# lat_stm_zybo_rev2.net
KiCad netlist of a schematic drawn in EAGLE
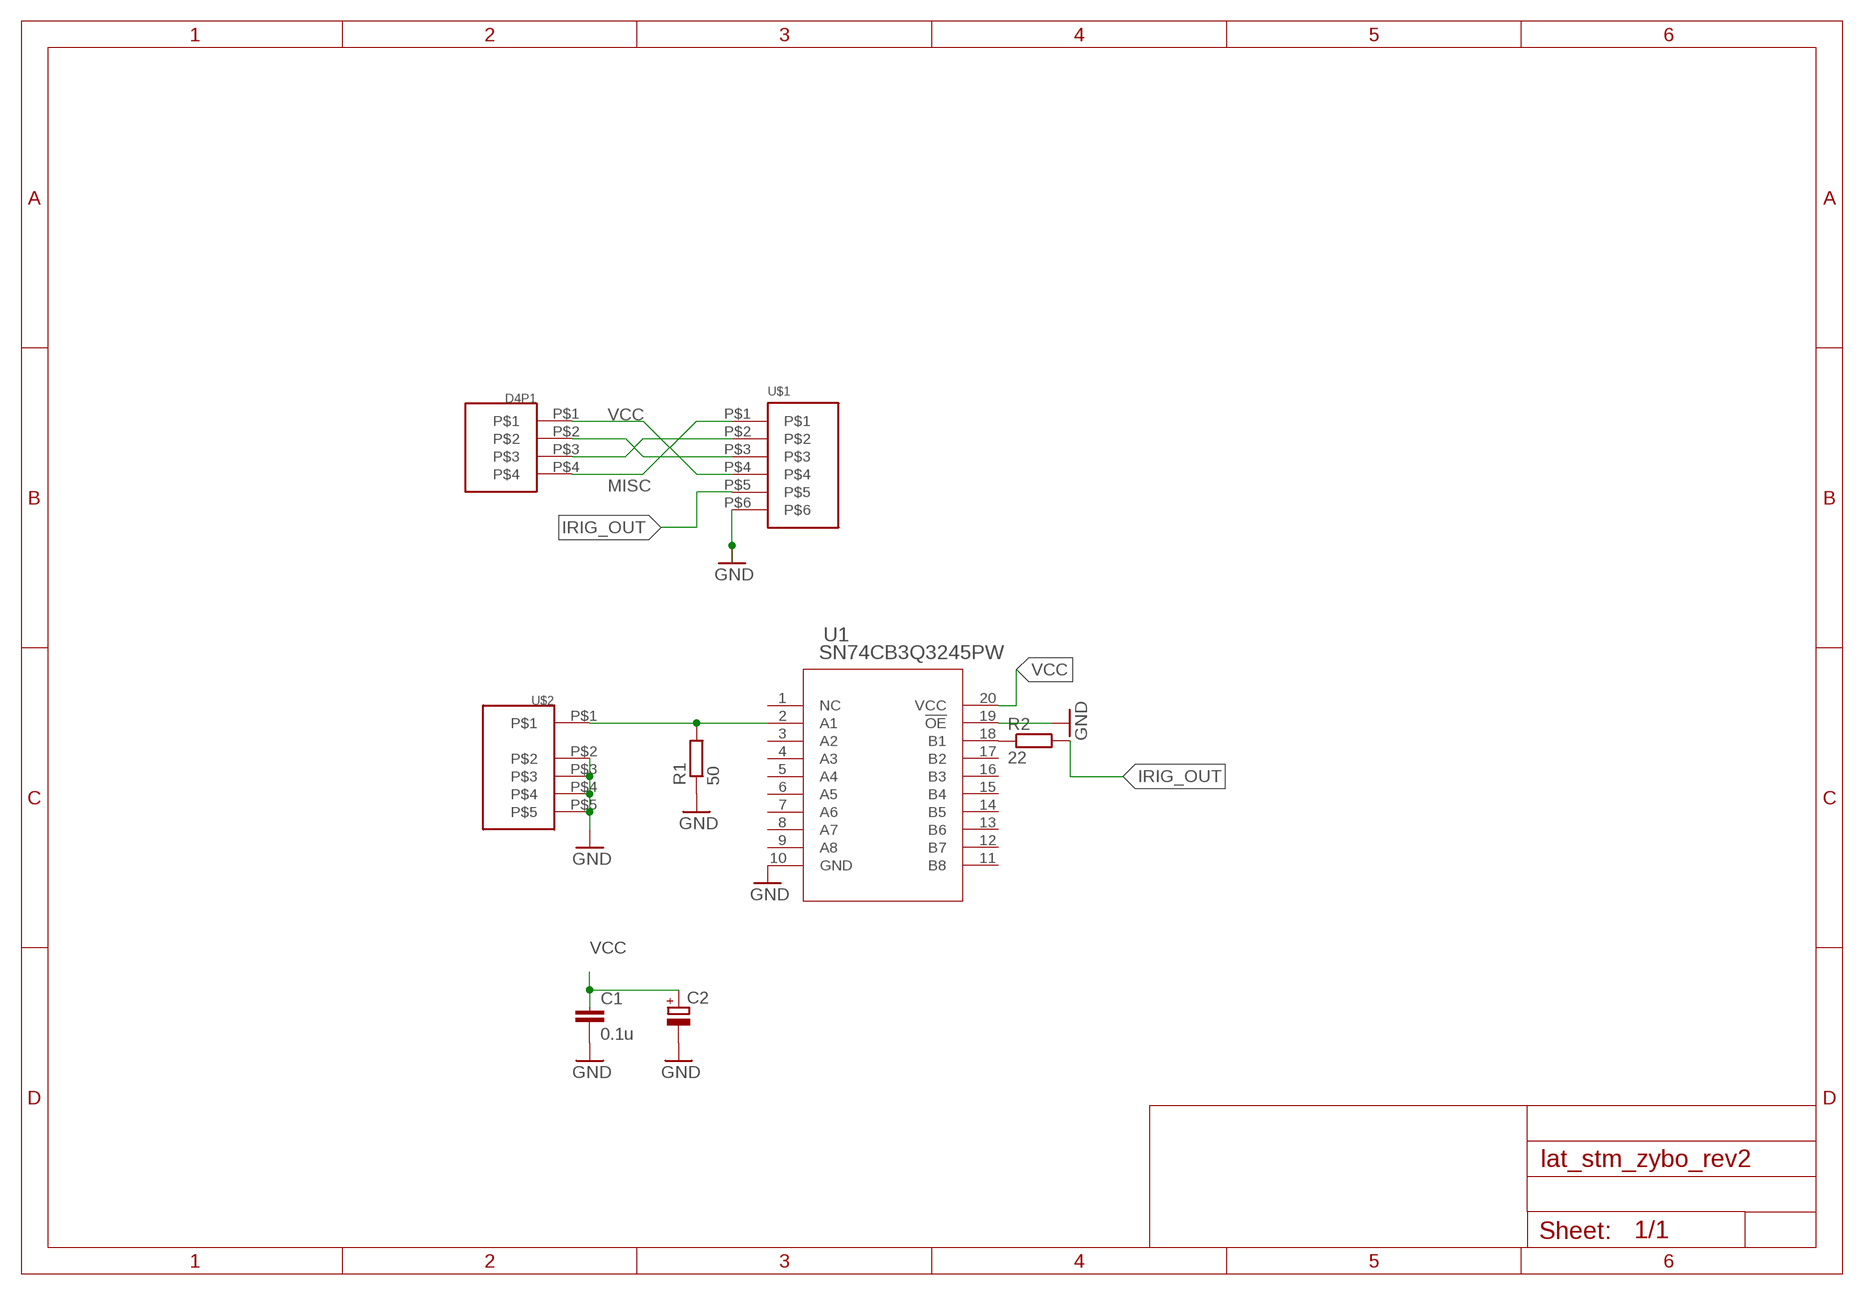
[diagram p0: schematic, sheet 1]

(export (version "E")
  (design (tool "Eeschema 10.0.6"))
  (components
    (comp (ref "C1")
      (value "0.1u")
      (footprint "eagle-import:C0603")
      (libsource (lib "eagle-import") (part "C-EUC0603"))
    )
    (comp (ref "C2")
      (value "CPOL-EUE2,5-6E")
      (footprint "eagle-import:E2,5-6E")
      (libsource (lib "eagle-import") (part "CPOL-EUE2,5-6E"))
    )
    (comp (ref "D4P1")
      (value "DF1E-4P")
      (footprint "eagle-import:DF1E-4P")
      (libsource (lib "eagle-import") (part "DF1E-4P"))
    )
    (comp (ref "R1")
      (value "50")
      (footprint "eagle-import:R0603")
      (libsource (lib "eagle-import") (part "R-EU_R0603"))
    )
    (comp (ref "R2")
      (value "22")
      (footprint "eagle-import:R0603")
      (libsource (lib "eagle-import") (part "R-EU_R0603"))
    )
    (comp (ref "U$1")
      (value "DF1E-6P")
      (footprint "eagle-import:DF1E-6P")
      (libsource (lib "eagle-import") (part "DF1E-6P"))
    )
    (comp (ref "U$2")
      (value "LEMO_CON")
      (footprint "eagle-import:LEMO_CON")
      (libsource (lib "eagle-import") (part "LEMO_CON"))
    )
    (comp (ref "U1")
      (value "SN74CB3Q3245PW")
      (footprint "eagle-import:PW20")
      (fields
        (field (name "GENERIC_PART_NUMBER") "SN74CB3Q3245")
        (field (name "MANUFACTURER") "Texas Instruments")
      )
      (libsource (lib "eagle-import") (part "SN74CB3Q3245PW"))
    )
  )
  (nets
    (net (code "1") (name "/MISC") (class "Default")
      (node (ref "D4P1") (pin "P$4") (pinfunction "P$4_P$4") (pintype "bidirectional"))
      (node (ref "U$1") (pin "P$1") (pinfunction "P$1_P$1") (pintype "bidirectional"))
    )
    (net (code "2") (name "GND") (class "Default")
      (node (ref "C1") (pin "2") (pinfunction "2_2") (pintype "passive"))
      (node (ref "C2") (pin "-") (pinfunction "-_-") (pintype "passive"))
      (node (ref "R1") (pin "1") (pinfunction "1_1") (pintype "passive"))
      (node (ref "U$1") (pin "P$6") (pinfunction "P$6_P$6") (pintype "bidirectional"))
      (node (ref "U$2") (pin "P$2") (pinfunction "P$2_P$2") (pintype "bidirectional"))
      (node (ref "U$2") (pin "P$3") (pinfunction "P$3_P$3") (pintype "bidirectional"))
      (node (ref "U$2") (pin "P$4") (pinfunction "P$4_P$4") (pintype "bidirectional"))
      (node (ref "U$2") (pin "P$5") (pinfunction "P$5_P$5") (pintype "bidirectional"))
      (node (ref "U1") (pin "10") (pinfunction "GND_10") (pintype "power_in"))
      (node (ref "U1") (pin "19") (pinfunction "~{OE}_19") (pintype "input"))
    )
    (net (code "3") (name "IRIG_OUT") (class "Default")
      (node (ref "R2") (pin "2") (pinfunction "2_2") (pintype "passive"))
      (node (ref "U$1") (pin "P$5") (pinfunction "P$5_P$5") (pintype "bidirectional"))
    )
    (net (code "4") (name "Net-(D4P1-PadP$2)") (class "Default")
      (node (ref "D4P1") (pin "P$2") (pinfunction "P$2_P$2") (pintype "bidirectional"))
      (node (ref "U$1") (pin "P$3") (pinfunction "P$3_P$3") (pintype "bidirectional"))
    )
    (net (code "5") (name "Net-(D4P1-PadP$3)") (class "Default")
      (node (ref "D4P1") (pin "P$3") (pinfunction "P$3_P$3") (pintype "bidirectional"))
      (node (ref "U$1") (pin "P$2") (pinfunction "P$2_P$2") (pintype "bidirectional"))
    )
    (net (code "6") (name "Net-(U1-A1)") (class "Default")
      (node (ref "R1") (pin "2") (pinfunction "2_2") (pintype "passive"))
      (node (ref "U$2") (pin "P$1") (pinfunction "P$1_P$1") (pintype "bidirectional"))
      (node (ref "U1") (pin "2") (pinfunction "A1_2") (pintype "bidirectional"))
    )
    (net (code "7") (name "Net-(U1-B1)") (class "Default")
      (node (ref "R2") (pin "1") (pinfunction "1_1") (pintype "passive"))
      (node (ref "U1") (pin "18") (pinfunction "B1_18") (pintype "bidirectional"))
    )
    (net (code "8") (name "VCC") (class "Default")
      (node (ref "C1") (pin "1") (pinfunction "1_1") (pintype "passive"))
      (node (ref "C2") (pin "+") (pinfunction "+_+") (pintype "passive"))
      (node (ref "D4P1") (pin "P$1") (pinfunction "P$1_P$1") (pintype "bidirectional"))
      (node (ref "U$1") (pin "P$4") (pinfunction "P$4_P$4") (pintype "bidirectional"))
      (node (ref "U1") (pin "20") (pinfunction "VCC_20") (pintype "power_in"))
    )
    (net (code "9") (name "unconnected-(U1-A2-Pad3)") (class "Default")
      (node (ref "U1") (pin "3") (pinfunction "A2_3") (pintype "bidirectional"))
    )
    (net (code "10") (name "unconnected-(U1-A3-Pad4)") (class "Default")
      (node (ref "U1") (pin "4") (pinfunction "A3_4") (pintype "bidirectional"))
    )
    (net (code "11") (name "unconnected-(U1-A4-Pad5)") (class "Default")
      (node (ref "U1") (pin "5") (pinfunction "A4_5") (pintype "bidirectional"))
    )
    (net (code "12") (name "unconnected-(U1-A5-Pad6)") (class "Default")
      (node (ref "U1") (pin "6") (pinfunction "A5_6") (pintype "bidirectional"))
    )
    (net (code "13") (name "unconnected-(U1-A6-Pad7)") (class "Default")
      (node (ref "U1") (pin "7") (pinfunction "A6_7") (pintype "bidirectional"))
    )
    (net (code "14") (name "unconnected-(U1-A7-Pad8)") (class "Default")
      (node (ref "U1") (pin "8") (pinfunction "A7_8") (pintype "bidirectional"))
    )
    (net (code "15") (name "unconnected-(U1-A8-Pad9)") (class "Default")
      (node (ref "U1") (pin "9") (pinfunction "A8_9") (pintype "bidirectional"))
    )
    (net (code "16") (name "unconnected-(U1-B2-Pad17)") (class "Default")
      (node (ref "U1") (pin "17") (pinfunction "B2_17") (pintype "bidirectional"))
    )
    (net (code "17") (name "unconnected-(U1-B3-Pad16)") (class "Default")
      (node (ref "U1") (pin "16") (pinfunction "B3_16") (pintype "bidirectional"))
    )
    (net (code "18") (name "unconnected-(U1-B4-Pad15)") (class "Default")
      (node (ref "U1") (pin "15") (pinfunction "B4_15") (pintype "bidirectional"))
    )
    (net (code "19") (name "unconnected-(U1-B5-Pad14)") (class "Default")
      (node (ref "U1") (pin "14") (pinfunction "B5_14") (pintype "bidirectional"))
    )
    (net (code "20") (name "unconnected-(U1-B6-Pad13)") (class "Default")
      (node (ref "U1") (pin "13") (pinfunction "B6_13") (pintype "bidirectional"))
    )
    (net (code "21") (name "unconnected-(U1-B7-Pad12)") (class "Default")
      (node (ref "U1") (pin "12") (pinfunction "B7_12") (pintype "bidirectional"))
    )
    (net (code "22") (name "unconnected-(U1-B8-Pad11)") (class "Default")
      (node (ref "U1") (pin "11") (pinfunction "B8_11") (pintype "bidirectional"))
    )
    (net (code "23") (name "unconnected-(U1-NC-Pad1)") (class "Default")
      (node (ref "U1") (pin "1") (pinfunction "NC_1") (pintype "passive"))
    )
  )
)
